# v1_0.net
KiCad netlist of a schematic drawn in Altium Designer
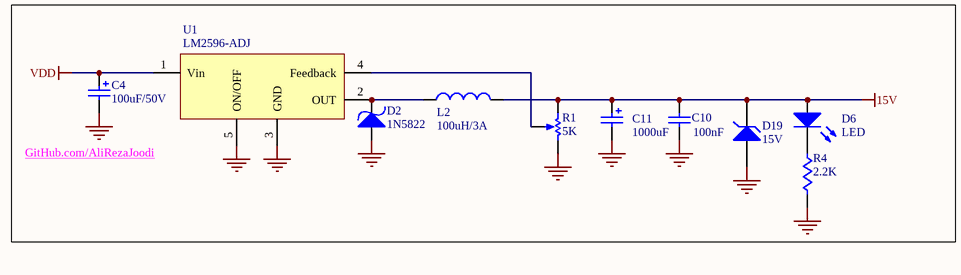
[diagram p0: v1.0.SchDoc]

(export (version "E")
  (design (tool "Eeschema 10.0.6"))
  (components
    (comp (ref "C4")
      (value "100uF/50V")
      (footprint "CAPPR3.05-3.81x6.35")
      (description "Polarized Capacitor (Radial)")
      (fields
        (field (name "MANUFACTURER") "Generic Components")
        (field (name "Comment") "Cap Pol1")
        (field (name "PUBLISHER") "Altium Limited")
      )
      (libsource (lib "Miscellaneous Devices") (part "Cap Pol1"))
    )
    (comp (ref "C10")
      (value "100nF")
      (footprint "CAPNTO2.54-3.05x1.78A")
      (description "Capacitor")
      (fields
        (field (name "MANUFACTURER") "Generic Components")
        (field (name "Comment") "Cap")
        (field (name "PUBLISHER") "Altium Limited")
      )
      (libsource (lib "Miscellaneous Devices") (part "Cap"))
    )
    (comp (ref "C11")
      (value "1000uF")
      (footprint "CAPPR5-10x12.5")
      (description "Polarized Capacitor (Radial)")
      (fields
        (field (name "MANUFACTURER") "Generic Components")
        (field (name "Comment") "Cap Pol1")
        (field (name "PUBLISHER") "Altium Limited")
      )
      (libsource (lib "Miscellaneous Devices") (part "Cap Pol1"))
    )
    (comp (ref "D2")
      (value "Diode_SCHOTTKY")
      (footprint "DIODE-0.7")
      (description "Diode")
      (fields
        (field (name "MANUFACTURER") "Generic Components")
        (field (name "DEVICE") "1N5822")
        (field (name "PUBLISHER") "Altium Limited")
      )
      (libsource (lib "my Libraries") (part "Diode_SCHOTTKY"))
    )
    (comp (ref "D6")
      (value "LED")
      (footprint "LED-5mm_Red")
      (description "Typical INFRARED GaAs LED")
      (fields (field (name "MANUFACTURER") "Generic Components") (field (name "PUBLISHER") "Altium Limited"))
      (libsource (lib "Miscellaneous Devices") (part "LED"))
    )
    (comp (ref "D19")
      (value "15V")
      (footprint "DIODE0.4_Glass")
      (description "Zener Diode")
      (fields
        (field (name "MANUFACTURER") "Generic Components")
        (field (name "Comment") "D Zener")
        (field (name "PUBLISHER") "Altium Limited")
      )
      (libsource (lib "Miscellaneous Devices") (part "D Zener"))
    )
    (comp (ref "L2")
      (value "100uH/3A")
      (footprint "INDUCTOR-2V")
      (description "Inductor")
      (fields (field (name "MANUFACTURER") "Generic Components") (field (name "PUBLISHER") "Altium Limited"))
      (libsource (lib "my Libraries") (part "Inductor"))
    )
    (comp (ref "R1")
      (value "5K")
      (footprint "VR4_")
      (description "Potentiometer")
      (fields
        (field (name "MANUFACTURER") "Generic Components")
        (field (name "Comment") "R16")
        (field (name "PUBLISHER") "Altium Limited")
      )
      (libsource (lib "my Libraries") (part "RPot1"))
    )
    (comp (ref "R4")
      (value "2.2K")
      (footprint "AXIAL-0.4")
      (description "Resistor")
      (fields
        (field (name "MANUFACTURER") "Generic Components")
        (field (name "Comment") "Res1")
        (field (name "PUBLISHER") "Altium Limited")
      )
      (libsource (lib "Miscellaneous Devices") (part "Res1"))
    )
    (comp (ref "U1")
      (value "LM2596-ADJ")
      (footprint "TO220-5H")
      (description "SWITCHER Power Converter 150 kHz3A Step-Down Voltage  Regulator")
      (libsource (lib "Other_Myself") (part "LM2596"))
    )
  )
  (nets
    (net (code "1") (name "15V") (class "Default")
      (node (ref "C10") (pin "2") (pinfunction "2_2") (pintype "passive"))
      (node (ref "C11") (pin "1") (pinfunction "1_1") (pintype "passive"))
      (node (ref "D19") (pin "2") (pinfunction "K_2") (pintype "passive"))
      (node (ref "D6") (pin "1") (pinfunction "A_1") (pintype "passive"))
      (node (ref "L2") (pin "2") (pinfunction "2_2") (pintype "passive"))
      (node (ref "R1") (pin "2") (pinfunction "BOT_2") (pintype "passive"))
    )
    (net (code "2") (name "GND") (class "Default")
      (node (ref "C10") (pin "1") (pinfunction "1_1") (pintype "passive"))
      (node (ref "C11") (pin "2") (pinfunction "2_2") (pintype "passive"))
      (node (ref "C4") (pin "2") (pinfunction "2_2") (pintype "passive"))
      (node (ref "D19") (pin "1") (pinfunction "A_1") (pintype "passive"))
      (node (ref "D2") (pin "1") (pinfunction "A_1") (pintype "passive"))
      (node (ref "R1") (pin "1") (pinfunction "TOP_1") (pintype "passive"))
      (node (ref "R4") (pin "2") (pinfunction "2_2") (pintype "passive"))
      (node (ref "U1") (pin "3") (pinfunction "GND_3") (pintype "passive"))
      (node (ref "U1") (pin "5") (pinfunction "ON/OFF_5") (pintype "passive"))
    )
    (net (code "3") (name "Net-(D2-K)") (class "Default")
      (node (ref "D2") (pin "2") (pinfunction "K_2") (pintype "passive"))
      (node (ref "L2") (pin "1") (pinfunction "1_1") (pintype "passive"))
      (node (ref "U1") (pin "2") (pinfunction "OUT_2") (pintype "passive"))
    )
    (net (code "4") (name "Net-(D6-K)") (class "Default")
      (node (ref "D6") (pin "2") (pinfunction "K_2") (pintype "passive"))
      (node (ref "R4") (pin "1") (pinfunction "1_1") (pintype "passive"))
    )
    (net (code "5") (name "Net-(R1-TAP)") (class "Default")
      (node (ref "R1") (pin "3") (pinfunction "TAP_3") (pintype "passive"))
      (node (ref "U1") (pin "4") (pinfunction "Feedback_4") (pintype "passive"))
    )
    (net (code "6") (name "VDD") (class "Default")
      (node (ref "C4") (pin "1") (pinfunction "1_1") (pintype "passive"))
      (node (ref "U1") (pin "1") (pinfunction "Vin_1") (pintype "passive"))
    )
  )
)
